# RasPi-BplusHAT_CamSlot.net
KiCad netlist of a schematic drawn in EAGLE
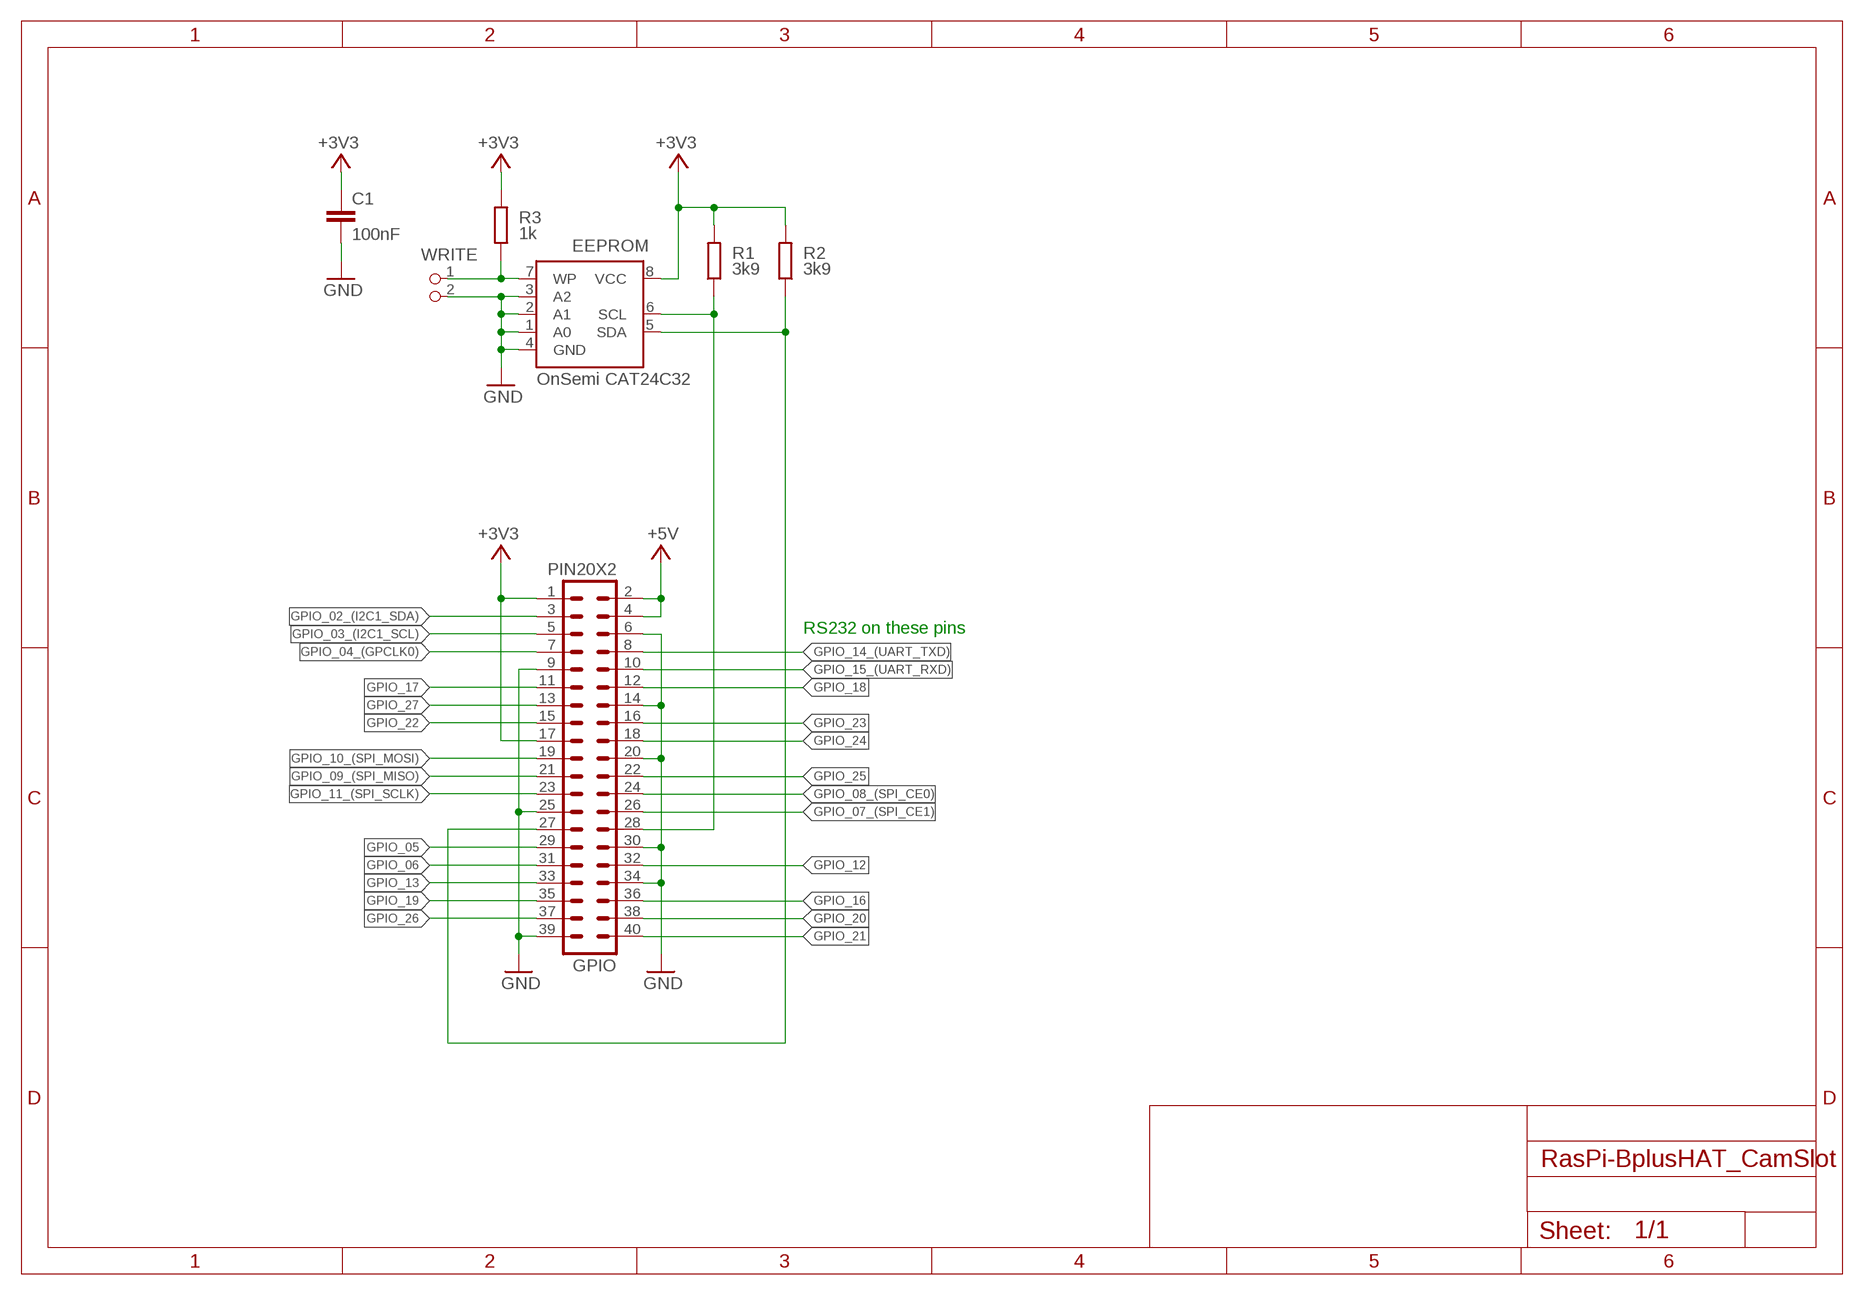
[diagram p0: schematic, sheet 1]

(export (version "E")
  (design (tool "Eeschema 10.0.6"))
  (components
    (comp (ref "C1")
      (value "100nF")
      (footprint "eagle-import:C0805K")
      (libsource (lib "eagle-import") (part "C-EUC0805K"))
    )
    (comp (ref "EEPROM")
      (value "OnSemi CAT24C32")
      (footprint "eagle-import:SOIC8")
      (libsource (lib "eagle-import") (part "EEPROM24"))
    )
    (comp (ref "GPIO")
      (value "PIN20X2")
      (footprint "eagle-import:PIN_20X2")
      (libsource (lib "eagle-import") (part "PIN20X2"))
    )
    (comp (ref "R1")
      (value "3k9")
      (footprint "eagle-import:M0805")
      (fields (field (name "TOLERANCE") "5%"))
      (libsource (lib "eagle-import") (part "R-EU_M0805"))
    )
    (comp (ref "R2")
      (value "3k9")
      (footprint "eagle-import:M0805")
      (fields (field (name "TOLERANCE") "5%"))
      (libsource (lib "eagle-import") (part "R-EU_M0805"))
    )
    (comp (ref "R3")
      (value "1k")
      (footprint "eagle-import:M0805")
      (fields (field (name "TOLERANCE") "5%"))
      (libsource (lib "eagle-import") (part "R-EU_M0805"))
    )
    (comp (ref "WRITE")
      (value "PIN2_100")
      (footprint "eagle-import:PIN_W_2")
      (libsource (lib "eagle-import") (part "PIN2_100"))
    )
  )
  (nets
    (net (code "1") (name "+3V3") (class "Default")
      (node (ref "C1") (pin "1") (pinfunction "1_1") (pintype "passive"))
      (node (ref "EEPROM") (pin "8") (pinfunction "VCC_8") (pintype "power_in"))
      (node (ref "GPIO") (pin "1") (pinfunction "1_1") (pintype "passive"))
      (node (ref "GPIO") (pin "17") (pinfunction "17_17") (pintype "passive"))
      (node (ref "R1") (pin "2") (pinfunction "2_2") (pintype "passive"))
      (node (ref "R2") (pin "2") (pinfunction "2_2") (pintype "passive"))
      (node (ref "R3") (pin "2") (pinfunction "2_2") (pintype "passive"))
    )
    (net (code "2") (name "+5V") (class "Default")
      (node (ref "GPIO") (pin "2") (pinfunction "2_2") (pintype "passive"))
      (node (ref "GPIO") (pin "4") (pinfunction "4_4") (pintype "passive"))
    )
    (net (code "3") (name "GND") (class "Default")
      (node (ref "C1") (pin "2") (pinfunction "2_2") (pintype "passive"))
      (node (ref "EEPROM") (pin "1") (pinfunction "A0_1") (pintype "input"))
      (node (ref "EEPROM") (pin "2") (pinfunction "A1_2") (pintype "input"))
      (node (ref "EEPROM") (pin "3") (pinfunction "A2_3") (pintype "input"))
      (node (ref "EEPROM") (pin "4") (pinfunction "GND_4") (pintype "power_in"))
      (node (ref "GPIO") (pin "14") (pinfunction "14_14") (pintype "passive"))
      (node (ref "GPIO") (pin "20") (pinfunction "20_20") (pintype "passive"))
      (node (ref "GPIO") (pin "25") (pinfunction "25_25") (pintype "passive"))
      (node (ref "GPIO") (pin "30") (pinfunction "30_30") (pintype "passive"))
      (node (ref "GPIO") (pin "34") (pinfunction "34_34") (pintype "passive"))
      (node (ref "GPIO") (pin "39") (pinfunction "39_39") (pintype "passive"))
      (node (ref "GPIO") (pin "6") (pinfunction "6_6") (pintype "passive"))
      (node (ref "GPIO") (pin "9") (pinfunction "9_9") (pintype "passive"))
      (node (ref "WRITE") (pin "2") (pinfunction "2_2") (pintype "passive"))
    )
    (net (code "4") (name "GPIO_02_(I2C1_SDA)") (class "Default")
      (node (ref "GPIO") (pin "3") (pinfunction "3_3") (pintype "passive"))
    )
    (net (code "5") (name "GPIO_03_(I2C1_SCL)") (class "Default")
      (node (ref "GPIO") (pin "5") (pinfunction "5_5") (pintype "passive"))
    )
    (net (code "6") (name "GPIO_04_(GPCLK0)") (class "Default")
      (node (ref "GPIO") (pin "7") (pinfunction "7_7") (pintype "passive"))
    )
    (net (code "7") (name "GPIO_05") (class "Default")
      (node (ref "GPIO") (pin "29") (pinfunction "29_29") (pintype "passive"))
    )
    (net (code "8") (name "GPIO_06") (class "Default")
      (node (ref "GPIO") (pin "31") (pinfunction "31_31") (pintype "passive"))
    )
    (net (code "9") (name "GPIO_07_(SPI_CE1)") (class "Default")
      (node (ref "GPIO") (pin "26") (pinfunction "26_26") (pintype "passive"))
    )
    (net (code "10") (name "GPIO_08_(SPI_CE0)") (class "Default")
      (node (ref "GPIO") (pin "24") (pinfunction "24_24") (pintype "passive"))
    )
    (net (code "11") (name "GPIO_09_(SPI_MISO)") (class "Default")
      (node (ref "GPIO") (pin "21") (pinfunction "21_21") (pintype "passive"))
    )
    (net (code "12") (name "GPIO_10_(SPI_MOSI)") (class "Default")
      (node (ref "GPIO") (pin "19") (pinfunction "19_19") (pintype "passive"))
    )
    (net (code "13") (name "GPIO_11_(SPI_SCLK)") (class "Default")
      (node (ref "GPIO") (pin "23") (pinfunction "23_23") (pintype "passive"))
    )
    (net (code "14") (name "GPIO_12") (class "Default")
      (node (ref "GPIO") (pin "32") (pinfunction "32_32") (pintype "passive"))
    )
    (net (code "15") (name "GPIO_13") (class "Default")
      (node (ref "GPIO") (pin "33") (pinfunction "33_33") (pintype "passive"))
    )
    (net (code "16") (name "GPIO_14_(UART_TXD)") (class "Default")
      (node (ref "GPIO") (pin "8") (pinfunction "8_8") (pintype "passive"))
    )
    (net (code "17") (name "GPIO_15_(UART_RXD)") (class "Default")
      (node (ref "GPIO") (pin "10") (pinfunction "10_10") (pintype "passive"))
    )
    (net (code "18") (name "GPIO_16") (class "Default")
      (node (ref "GPIO") (pin "36") (pinfunction "36_36") (pintype "passive"))
    )
    (net (code "19") (name "GPIO_17") (class "Default")
      (node (ref "GPIO") (pin "11") (pinfunction "11_11") (pintype "passive"))
    )
    (net (code "20") (name "GPIO_18") (class "Default")
      (node (ref "GPIO") (pin "12") (pinfunction "12_12") (pintype "passive"))
    )
    (net (code "21") (name "GPIO_19") (class "Default")
      (node (ref "GPIO") (pin "35") (pinfunction "35_35") (pintype "passive"))
    )
    (net (code "22") (name "GPIO_20") (class "Default")
      (node (ref "GPIO") (pin "38") (pinfunction "38_38") (pintype "passive"))
    )
    (net (code "23") (name "GPIO_21") (class "Default")
      (node (ref "GPIO") (pin "40") (pinfunction "40_40") (pintype "passive"))
    )
    (net (code "24") (name "GPIO_22") (class "Default")
      (node (ref "GPIO") (pin "15") (pinfunction "15_15") (pintype "passive"))
    )
    (net (code "25") (name "GPIO_23") (class "Default")
      (node (ref "GPIO") (pin "16") (pinfunction "16_16") (pintype "passive"))
    )
    (net (code "26") (name "GPIO_24") (class "Default")
      (node (ref "GPIO") (pin "18") (pinfunction "18_18") (pintype "passive"))
    )
    (net (code "27") (name "GPIO_25") (class "Default")
      (node (ref "GPIO") (pin "22") (pinfunction "22_22") (pintype "passive"))
    )
    (net (code "28") (name "GPIO_26") (class "Default")
      (node (ref "GPIO") (pin "37") (pinfunction "37_37") (pintype "passive"))
    )
    (net (code "29") (name "GPIO_27") (class "Default")
      (node (ref "GPIO") (pin "13") (pinfunction "13_13") (pintype "passive"))
    )
    (net (code "30") (name "Net-(EEPROM-SCL)") (class "Default")
      (node (ref "EEPROM") (pin "6") (pinfunction "SCL_6") (pintype "input"))
      (node (ref "GPIO") (pin "28") (pinfunction "28_28") (pintype "passive"))
      (node (ref "R1") (pin "1") (pinfunction "1_1") (pintype "passive"))
    )
    (net (code "31") (name "Net-(EEPROM-SDA)") (class "Default")
      (node (ref "EEPROM") (pin "5") (pinfunction "SDA_5") (pintype "bidirectional"))
      (node (ref "GPIO") (pin "27") (pinfunction "27_27") (pintype "passive"))
      (node (ref "R2") (pin "1") (pinfunction "1_1") (pintype "passive"))
    )
    (net (code "32") (name "Net-(EEPROM-WP)") (class "Default")
      (node (ref "EEPROM") (pin "7") (pinfunction "WP_7") (pintype "input"))
      (node (ref "R3") (pin "1") (pinfunction "1_1") (pintype "passive"))
      (node (ref "WRITE") (pin "1") (pinfunction "1_1") (pintype "passive"))
    )
  )
)
